# Arduino_CTRL.net
KiCad netlist of a schematic drawn in Altium Designer
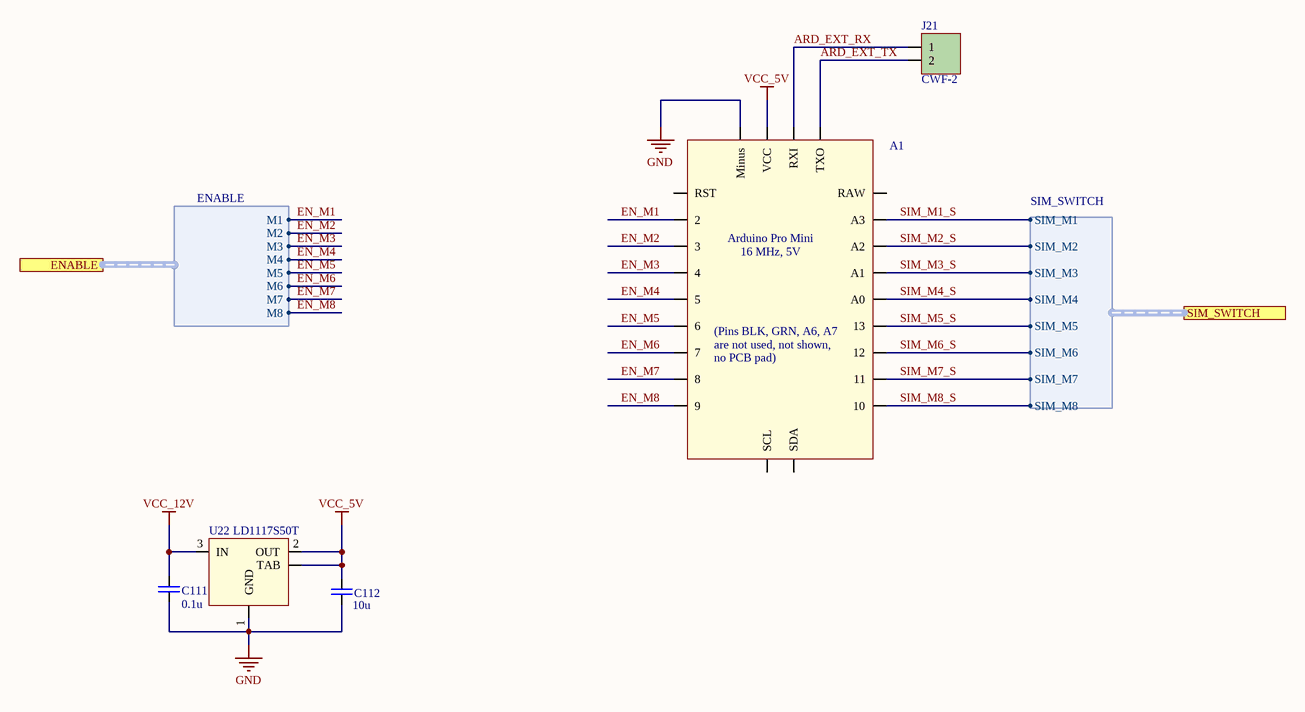
[diagram p0: Arduino_CTRL.SchDoc]

(export (version "E")
  (design (tool "Eeschema 10.0.6"))
  (components
    (comp (ref "A1")
      (value "Интегрированный модуль Arduino Pro Mini, 16 МГц, 5В PBS-12 (DS1023-1x12)(x2) PBS-4 (DS1023-1x4)PartNumber3")
      (footprint "ThoughHole_Components:Arduino Pro Mini Reduced")
      (description "Arduino Pro Mini 16MHz 5v")
      (libsource (lib "Connectors") (part "Arduino Pro Mini 16MHz 5v Reduced"))
    )
    (comp (ref "C111")
      (value "0.1u")
      (footprint "SMD_components:C0402")
      (description "Chip Capacitor 0402")
      (fields (field (name "VOLTAGE") "25В") (field (name "TOLERANCE") "10%"))
      (libsource (lib "Passives") (part "C0402"))
    )
    (comp (ref "C112")
      (value "10u")
      (footprint "SMD_components:C0805")
      (description "Chip Capacitor 0805")
      (fields (field (name "VOLTAGE") "16В") (field (name "TOLERANCE") "10%"))
      (libsource (lib "Passives") (part "C0805"))
    )
    (comp (ref "J21")
      (value "CWF-2")
      (footprint "Connectors:CWF-2")
      (fields
        (field (name "MANUFACTURER") "(China)")
        (field (name "PARTNUMBER") "CWF-2 (DS1069-2 M)")
        (field (name "Comment") "Разъём (вилка), CWF-2 (DS1069-2 M)")
      )
      (libsource (lib "Connectors") (part "CWF-2"))
    )
    (comp (ref "U22")
      (value "Микросхема, LD1117S50T")
      (footprint "SMD_components:SOT223")
      (description "0.8-A, Positive Fixed-Voltage, Low-Dropout Regulator")
      (fields (field (name "MANUFACTURER") "ST Microelectronics") (field (name "PARTNUMBER") "LD1117S50T"))
      (libsource (lib "IC") (part "LD1117S50TR"))
    )
  )
  (nets
    (net (code "3") (name "/ARD_EXT_RX") (class "Default")
      (node (ref "A1") (pin "RXI") (pinfunction "RXI_RXI") (pintype "passive"))
      (node (ref "J21") (pin "1") (pinfunction "1_1") (pintype "passive"))
    )
    (net (code "4") (name "/ARD_EXT_TX") (class "Default")
      (node (ref "A1") (pin "TXO") (pinfunction "TXO_TXO") (pintype "passive"))
      (node (ref "J21") (pin "2") (pinfunction "2_2") (pintype "passive"))
    )
    (net (code "5") (name "/EN_M1") (class "Default")
      (node (ref "A1") (pin "2") (pinfunction "2_2") (pintype "passive"))
    )
    (net (code "6") (name "/EN_M2") (class "Default")
      (node (ref "A1") (pin "3") (pinfunction "3_3") (pintype "passive"))
    )
    (net (code "7") (name "/EN_M3") (class "Default")
      (node (ref "A1") (pin "4") (pinfunction "4_4") (pintype "passive"))
    )
    (net (code "8") (name "/EN_M4") (class "Default")
      (node (ref "A1") (pin "5") (pinfunction "5_5") (pintype "passive"))
    )
    (net (code "9") (name "/EN_M5") (class "Default")
      (node (ref "A1") (pin "6") (pinfunction "6_6") (pintype "passive"))
    )
    (net (code "10") (name "/EN_M6") (class "Default")
      (node (ref "A1") (pin "7") (pinfunction "7_7") (pintype "passive"))
    )
    (net (code "11") (name "/EN_M7") (class "Default")
      (node (ref "A1") (pin "8") (pinfunction "8_8") (pintype "passive"))
    )
    (net (code "12") (name "/EN_M8") (class "Default")
      (node (ref "A1") (pin "9") (pinfunction "9_9") (pintype "passive"))
    )
    (net (code "13") (name "/SIM_M1_S") (class "Default")
      (node (ref "A1") (pin "A3") (pinfunction "A3_A3") (pintype "passive"))
    )
    (net (code "14") (name "/SIM_M2_S") (class "Default")
      (node (ref "A1") (pin "A2") (pinfunction "A2_A2") (pintype "passive"))
    )
    (net (code "15") (name "/SIM_M3_S") (class "Default")
      (node (ref "A1") (pin "A1") (pinfunction "A1_A1") (pintype "passive"))
    )
    (net (code "16") (name "/SIM_M4_S") (class "Default")
      (node (ref "A1") (pin "A0") (pinfunction "A0_A0") (pintype "passive"))
    )
    (net (code "17") (name "/SIM_M5_S") (class "Default")
      (node (ref "A1") (pin "13") (pinfunction "13_13") (pintype "passive"))
    )
    (net (code "18") (name "/SIM_M6_S") (class "Default")
      (node (ref "A1") (pin "12") (pinfunction "12_12") (pintype "passive"))
    )
    (net (code "19") (name "/SIM_M7_S") (class "Default")
      (node (ref "A1") (pin "11") (pinfunction "11_11") (pintype "passive"))
    )
    (net (code "20") (name "/SIM_M8_S") (class "Default")
      (node (ref "A1") (pin "10") (pinfunction "10_10") (pintype "passive"))
    )
    (net (code "23") (name "GND") (class "Default")
      (node (ref "A1") (pin "Minus") (pinfunction "Minus_Minus") (pintype "passive"))
      (node (ref "C111") (pin "2") (pinfunction "2_2") (pintype "passive"))
      (node (ref "C112") (pin "2") (pinfunction "2_2") (pintype "passive"))
      (node (ref "U22") (pin "1") (pinfunction "GND_1") (pintype "power_in"))
    )
    (net (code "24") (name "VCC_5V") (class "Default")
      (node (ref "A1") (pin "VCC") (pinfunction "VCC_VCC") (pintype "passive"))
      (node (ref "C112") (pin "1") (pinfunction "1_1") (pintype "passive"))
      (node (ref "U22") (pin "2") (pinfunction "OUT_2") (pintype "power_in"))
      (node (ref "U22") (pin "4") (pinfunction "TAB_4") (pintype "passive"))
    )
    (net (code "25") (name "VCC_12V") (class "Default")
      (node (ref "C111") (pin "1") (pinfunction "1_1") (pintype "passive"))
      (node (ref "U22") (pin "3") (pinfunction "IN_3") (pintype "power_in"))
    )
    (net (code "26") (name "unconnected-(A1-PadRAW)") (class "Default")
      (node (ref "A1") (pin "RAW") (pinfunction "RAW_RAW") (pintype "passive"))
    )
    (net (code "27") (name "unconnected-(A1-PadRST)") (class "Default")
      (node (ref "A1") (pin "RST") (pinfunction "RST_RST") (pintype "passive"))
    )
    (net (code "28") (name "unconnected-(A1-SCL-PadA5)") (class "Default")
      (node (ref "A1") (pin "A5") (pinfunction "SCL_A5") (pintype "passive"))
    )
    (net (code "29") (name "unconnected-(A1-SDA-PadA4)") (class "Default")
      (node (ref "A1") (pin "A4") (pinfunction "SDA_A4") (pintype "passive"))
    )
  )
)
